# XPDR_Board_1.net
KiCad netlist of a schematic drawn in EAGLE
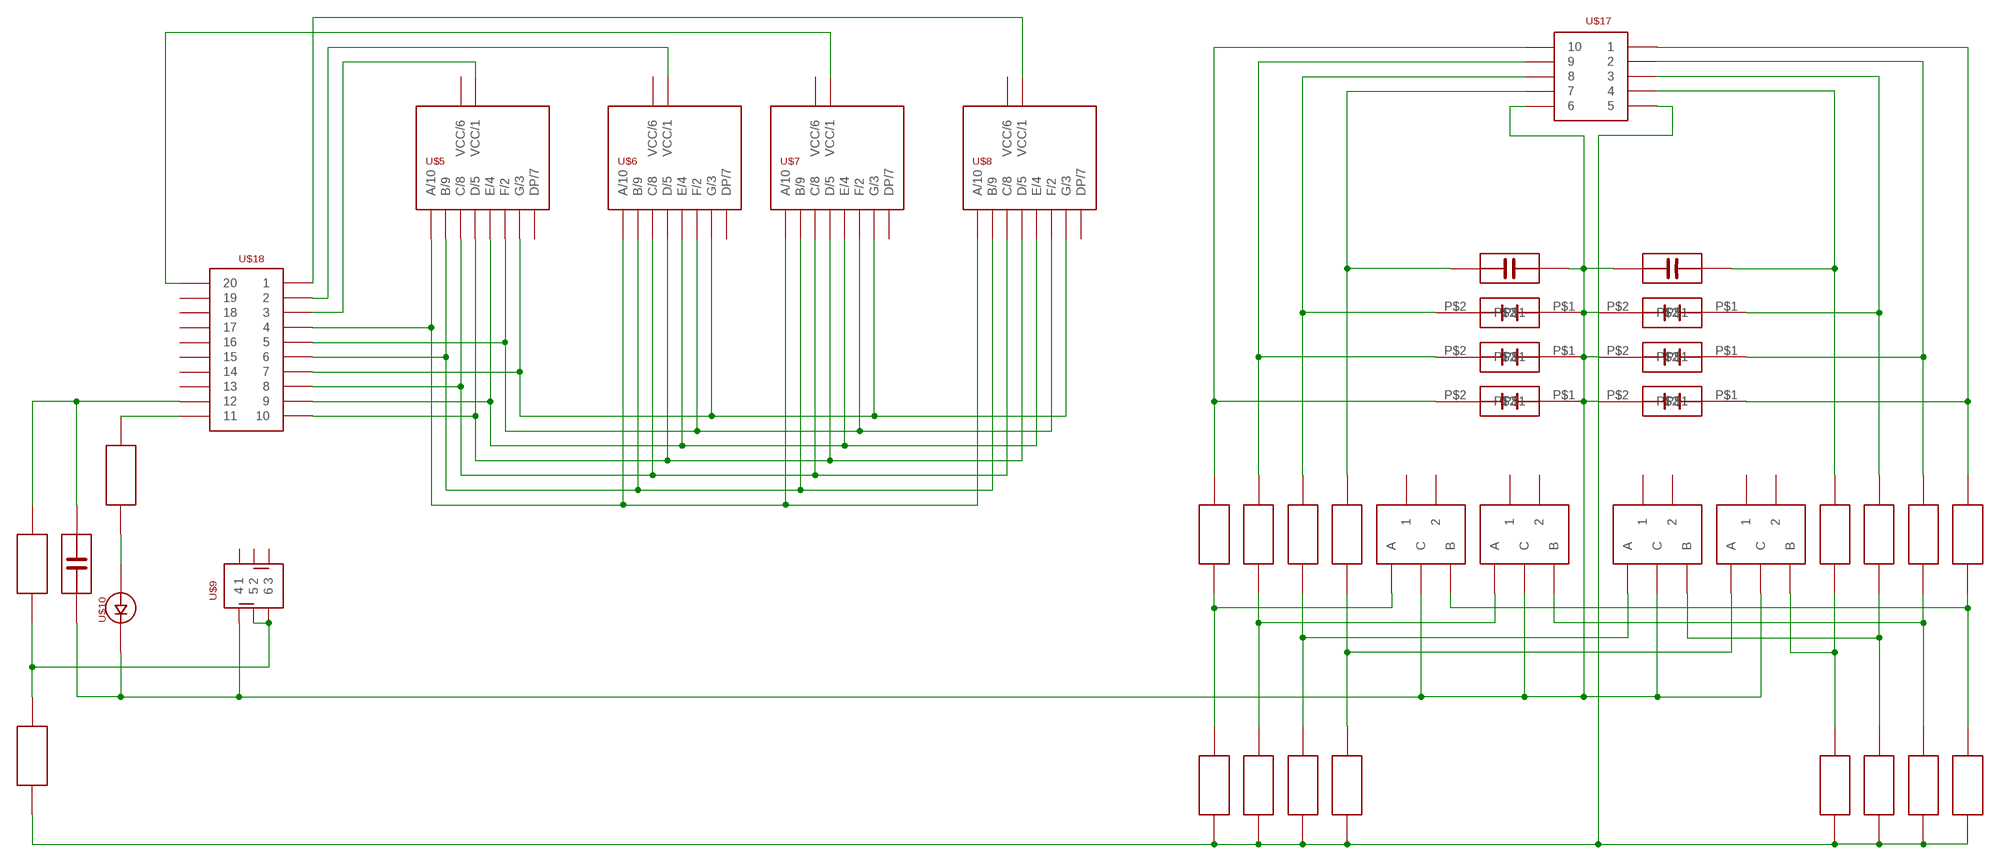
[diagram p0: schematic, sheet 1]

(export (version "E")
  (design (tool "Eeschema 10.0.6"))
  (components
    (comp (ref "U$1")
      (value "PEC11R")
      (footprint "eagle-import:PEC11R")
      (libsource (lib "eagle-import") (part "PEC11R"))
    )
    (comp (ref "U$2")
      (value "PEC11R")
      (footprint "eagle-import:PEC11R")
      (libsource (lib "eagle-import") (part "PEC11R"))
    )
    (comp (ref "U$3")
      (value "PEC11R")
      (footprint "eagle-import:PEC11R")
      (libsource (lib "eagle-import") (part "PEC11R"))
    )
    (comp (ref "U$4")
      (value "PEC11R")
      (footprint "eagle-import:PEC11R")
      (libsource (lib "eagle-import") (part "PEC11R"))
    )
    (comp (ref "U$5")
      (value "SA3611EWA")
      (footprint "eagle-import:SA3611EWA")
      (libsource (lib "eagle-import") (part "SA3611EWA"))
    )
    (comp (ref "U$6")
      (value "SA3611EWA")
      (footprint "eagle-import:SA3611EWA")
      (libsource (lib "eagle-import") (part "SA3611EWA"))
    )
    (comp (ref "U$7")
      (value "SA3611EWA")
      (footprint "eagle-import:SA3611EWA")
      (libsource (lib "eagle-import") (part "SA3611EWA"))
    )
    (comp (ref "U$8")
      (value "SA3611EWA")
      (footprint "eagle-import:SA3611EWA")
      (libsource (lib "eagle-import") (part "SA3611EWA"))
    )
    (comp (ref "U$9")
      (value "P1-0S")
      (footprint "eagle-import:P1-0S")
      (libsource (lib "eagle-import") (part "P1-0S"))
    )
    (comp (ref "U$10")
      (value "LED_5MM")
      (footprint "eagle-import:LED_5MM")
      (libsource (lib "eagle-import") (part "LED_5MM"))
    )
    (comp (ref "U$11")
      (value "REZISTOR")
      (footprint "eagle-import:REZISTOR")
      (libsource (lib "eagle-import") (part "REZISTOR"))
    )
    (comp (ref "U$12")
      (value "REZISTOR")
      (footprint "eagle-import:REZISTOR")
      (libsource (lib "eagle-import") (part "REZISTOR"))
    )
    (comp (ref "U$13")
      (value "REZISTOR")
      (footprint "eagle-import:REZISTOR")
      (libsource (lib "eagle-import") (part "REZISTOR"))
    )
    (comp (ref "U$14")
      (value "REZISTOR")
      (footprint "eagle-import:REZISTOR")
      (libsource (lib "eagle-import") (part "REZISTOR"))
    )
    (comp (ref "U$15")
      (value "REZISTOR")
      (footprint "eagle-import:REZISTOR")
      (libsource (lib "eagle-import") (part "REZISTOR"))
    )
    (comp (ref "U$16")
      (value "REZISTOR")
      (footprint "eagle-import:REZISTOR")
      (libsource (lib "eagle-import") (part "REZISTOR"))
    )
    (comp (ref "U$17")
      (value "LISTA_2X5")
      (footprint "eagle-import:LISTA_2X5")
      (libsource (lib "eagle-import") (part "LISTA_2X5"))
    )
    (comp (ref "U$18")
      (value "LISTA_2X10")
      (footprint "eagle-import:LISTA_2X10")
      (libsource (lib "eagle-import") (part "LISTA_2X10"))
    )
    (comp (ref "U$19")
      (value "REZISTOR")
      (footprint "eagle-import:REZISTOR")
      (libsource (lib "eagle-import") (part "REZISTOR"))
    )
    (comp (ref "U$20")
      (value "REZISTOR")
      (footprint "eagle-import:REZISTOR")
      (libsource (lib "eagle-import") (part "REZISTOR"))
    )
    (comp (ref "U$21")
      (value "REZISTOR")
      (footprint "eagle-import:REZISTOR")
      (libsource (lib "eagle-import") (part "REZISTOR"))
    )
    (comp (ref "U$22")
      (value "REZISTOR")
      (footprint "eagle-import:REZISTOR")
      (libsource (lib "eagle-import") (part "REZISTOR"))
    )
    (comp (ref "U$23")
      (value "REZISTOR")
      (footprint "eagle-import:REZISTOR")
      (libsource (lib "eagle-import") (part "REZISTOR"))
    )
    (comp (ref "U$24")
      (value "REZISTOR")
      (footprint "eagle-import:REZISTOR")
      (libsource (lib "eagle-import") (part "REZISTOR"))
    )
    (comp (ref "U$25")
      (value "REZISTOR")
      (footprint "eagle-import:REZISTOR")
      (libsource (lib "eagle-import") (part "REZISTOR"))
    )
    (comp (ref "U$26")
      (value "REZISTOR")
      (footprint "eagle-import:REZISTOR")
      (libsource (lib "eagle-import") (part "REZISTOR"))
    )
    (comp (ref "U$27")
      (value "REZISTOR")
      (footprint "eagle-import:REZISTOR")
      (libsource (lib "eagle-import") (part "REZISTOR"))
    )
    (comp (ref "U$28")
      (value "REZISTOR")
      (footprint "eagle-import:REZISTOR")
      (libsource (lib "eagle-import") (part "REZISTOR"))
    )
    (comp (ref "U$29")
      (value "KONDENZATOR_SIROKY")
      (footprint "eagle-import:KONDENZATOR_SIROKY")
      (libsource (lib "eagle-import") (part "KONDENZATOR_SIROKY"))
    )
    (comp (ref "U$30")
      (value "REZISTOR")
      (footprint "eagle-import:REZISTOR")
      (libsource (lib "eagle-import") (part "REZISTOR"))
    )
    (comp (ref "U$31")
      (value "REZISTOR")
      (footprint "eagle-import:REZISTOR")
      (libsource (lib "eagle-import") (part "REZISTOR"))
    )
    (comp (ref "U$32")
      (value "KONDENZATOR_SIROKY")
      (footprint "eagle-import:KONDENZATOR_SIROKY")
      (libsource (lib "eagle-import") (part "KONDENZATOR_SIROKY"))
    )
    (comp (ref "U$33")
      (value "KONDENZATOR_SIROKY")
      (footprint "eagle-import:KONDENZATOR_SIROKY")
      (libsource (lib "eagle-import") (part "KONDENZATOR_SIROKY"))
    )
    (comp (ref "U$34")
      (value "KONDENZATOR")
      (footprint "eagle-import:KONDENZATOR")
      (libsource (lib "eagle-import") (part "KONDENZATOR"))
    )
    (comp (ref "U$35")
      (value "KONDENZATOR_SIROKY")
      (footprint "eagle-import:KONDENZATOR_SIROKY")
      (libsource (lib "eagle-import") (part "KONDENZATOR_SIROKY"))
    )
    (comp (ref "U$36")
      (value "KONDENZATOR_SIROKY")
      (footprint "eagle-import:KONDENZATOR_SIROKY")
      (libsource (lib "eagle-import") (part "KONDENZATOR_SIROKY"))
    )
    (comp (ref "U$37")
      (value "KONDENZATOR_SIROKY")
      (footprint "eagle-import:KONDENZATOR_SIROKY")
      (libsource (lib "eagle-import") (part "KONDENZATOR_SIROKY"))
    )
    (comp (ref "U$38")
      (value "KONDENZATOR")
      (footprint "eagle-import:KONDENZATOR")
      (libsource (lib "eagle-import") (part "KONDENZATOR"))
    )
    (comp (ref "U$39")
      (value "KONDENZATOR")
      (footprint "eagle-import:KONDENZATOR")
      (libsource (lib "eagle-import") (part "KONDENZATOR"))
    )
    (comp (ref "U$40")
      (value "REZISTOR")
      (footprint "eagle-import:REZISTOR")
      (libsource (lib "eagle-import") (part "REZISTOR"))
    )
  )
  (nets
    (net (code "1") (name "Net-(U$1-PadA)") (class "Default")
      (node (ref "U$1") (pin "A") (pinfunction "A_A") (pintype "bidirectional"))
      (node (ref "U$11") (pin "P$1") (pinfunction "P$1_P$1") (pintype "bidirectional"))
      (node (ref "U$28") (pin "P$1") (pinfunction "P$1_P$1") (pintype "bidirectional"))
    )
    (net (code "2") (name "Net-(U$1-PadB)") (class "Default")
      (node (ref "U$1") (pin "B") (pinfunction "B_B") (pintype "bidirectional"))
      (node (ref "U$12") (pin "P$1") (pinfunction "P$1_P$1") (pintype "bidirectional"))
      (node (ref "U$27") (pin "P$1") (pinfunction "P$1_P$1") (pintype "bidirectional"))
    )
    (net (code "3") (name "Net-(U$1-PadC)") (class "Default")
      (node (ref "U$1") (pin "C") (pinfunction "C_C") (pintype "bidirectional"))
      (node (ref "U$10") (pin "P$2") (pinfunction "P$2_P$2") (pintype "bidirectional"))
      (node (ref "U$17") (pin "6") (pinfunction "6_6") (pintype "bidirectional"))
      (node (ref "U$2") (pin "C") (pinfunction "C_C") (pintype "bidirectional"))
      (node (ref "U$29") (pin "P$1") (pinfunction "P$1_P$1") (pintype "bidirectional"))
      (node (ref "U$3") (pin "C") (pinfunction "C_C") (pintype "bidirectional"))
      (node (ref "U$32") (pin "P$1") (pinfunction "P$1_P$1") (pintype "bidirectional"))
      (node (ref "U$33") (pin "P$1") (pinfunction "P$1_P$1") (pintype "bidirectional"))
      (node (ref "U$34") (pin "P$1") (pinfunction "P$1_P$1") (pintype "bidirectional"))
      (node (ref "U$35") (pin "P$2") (pinfunction "P$2_P$2") (pintype "bidirectional"))
      (node (ref "U$36") (pin "P$2") (pinfunction "P$2_P$2") (pintype "bidirectional"))
      (node (ref "U$37") (pin "P$2") (pinfunction "P$2_P$2") (pintype "bidirectional"))
      (node (ref "U$38") (pin "P$2") (pinfunction "P$2_P$2") (pintype "bidirectional"))
      (node (ref "U$39") (pin "P$2") (pinfunction "P$2_P$2") (pintype "bidirectional"))
      (node (ref "U$4") (pin "C") (pinfunction "C_C") (pintype "bidirectional"))
      (node (ref "U$9") (pin "4") (pinfunction "4_4") (pintype "bidirectional"))
    )
    (net (code "4") (name "Net-(U$5-A{slash}10)") (class "Default")
      (node (ref "U$18") (pin "4") (pinfunction "4_4") (pintype "bidirectional"))
      (node (ref "U$5") (pin "10") (pinfunction "A/10_10") (pintype "bidirectional"))
      (node (ref "U$6") (pin "10") (pinfunction "A/10_10") (pintype "bidirectional"))
      (node (ref "U$7") (pin "10") (pinfunction "A/10_10") (pintype "bidirectional"))
      (node (ref "U$8") (pin "10") (pinfunction "A/10_10") (pintype "bidirectional"))
    )
    (net (code "5") (name "Net-(U$5-B{slash}9)") (class "Default")
      (node (ref "U$18") (pin "6") (pinfunction "6_6") (pintype "bidirectional"))
      (node (ref "U$5") (pin "9") (pinfunction "B/9_9") (pintype "bidirectional"))
      (node (ref "U$6") (pin "9") (pinfunction "B/9_9") (pintype "bidirectional"))
      (node (ref "U$7") (pin "9") (pinfunction "B/9_9") (pintype "bidirectional"))
      (node (ref "U$8") (pin "9") (pinfunction "B/9_9") (pintype "bidirectional"))
    )
    (net (code "6") (name "Net-(U$5-C{slash}8)") (class "Default")
      (node (ref "U$18") (pin "8") (pinfunction "8_8") (pintype "bidirectional"))
      (node (ref "U$5") (pin "8") (pinfunction "C/8_8") (pintype "bidirectional"))
      (node (ref "U$6") (pin "8") (pinfunction "C/8_8") (pintype "bidirectional"))
      (node (ref "U$7") (pin "8") (pinfunction "C/8_8") (pintype "bidirectional"))
      (node (ref "U$8") (pin "8") (pinfunction "C/8_8") (pintype "bidirectional"))
    )
    (net (code "7") (name "Net-(U$5-D{slash}5)") (class "Default")
      (node (ref "U$18") (pin "10") (pinfunction "10_10") (pintype "bidirectional"))
      (node (ref "U$5") (pin "5") (pinfunction "D/5_5") (pintype "bidirectional"))
      (node (ref "U$6") (pin "5") (pinfunction "D/5_5") (pintype "bidirectional"))
      (node (ref "U$7") (pin "5") (pinfunction "D/5_5") (pintype "bidirectional"))
      (node (ref "U$8") (pin "5") (pinfunction "D/5_5") (pintype "bidirectional"))
    )
    (net (code "8") (name "Net-(U$5-E{slash}4)") (class "Default")
      (node (ref "U$18") (pin "9") (pinfunction "9_9") (pintype "bidirectional"))
      (node (ref "U$5") (pin "4") (pinfunction "E/4_4") (pintype "bidirectional"))
      (node (ref "U$6") (pin "4") (pinfunction "E/4_4") (pintype "bidirectional"))
      (node (ref "U$7") (pin "4") (pinfunction "E/4_4") (pintype "bidirectional"))
      (node (ref "U$8") (pin "4") (pinfunction "E/4_4") (pintype "bidirectional"))
    )
    (net (code "9") (name "Net-(U$5-F{slash}2)") (class "Default")
      (node (ref "U$18") (pin "5") (pinfunction "5_5") (pintype "bidirectional"))
      (node (ref "U$5") (pin "2") (pinfunction "F/2_2") (pintype "bidirectional"))
      (node (ref "U$6") (pin "2") (pinfunction "F/2_2") (pintype "bidirectional"))
      (node (ref "U$7") (pin "2") (pinfunction "F/2_2") (pintype "bidirectional"))
      (node (ref "U$8") (pin "2") (pinfunction "F/2_2") (pintype "bidirectional"))
    )
    (net (code "10") (name "Net-(U$5-G{slash}3)") (class "Default")
      (node (ref "U$18") (pin "7") (pinfunction "7_7") (pintype "bidirectional"))
      (node (ref "U$5") (pin "3") (pinfunction "G/3_3") (pintype "bidirectional"))
      (node (ref "U$6") (pin "3") (pinfunction "G/3_3") (pintype "bidirectional"))
      (node (ref "U$7") (pin "3") (pinfunction "G/3_3") (pintype "bidirectional"))
      (node (ref "U$8") (pin "3") (pinfunction "G/3_3") (pintype "bidirectional"))
    )
    (net (code "11") (name "Net-(U$5-VCC{slash}1)") (class "Default")
      (node (ref "U$18") (pin "3") (pinfunction "3_3") (pintype "bidirectional"))
      (node (ref "U$5") (pin "1") (pinfunction "VCC/1_1") (pintype "bidirectional"))
    )
    (net (code "12") (name "Net-(U$6-VCC{slash}1)") (class "Default")
      (node (ref "U$18") (pin "2") (pinfunction "2_2") (pintype "bidirectional"))
      (node (ref "U$6") (pin "1") (pinfunction "VCC/1_1") (pintype "bidirectional"))
    )
    (net (code "13") (name "Net-(U$7-VCC{slash}1)") (class "Default")
      (node (ref "U$18") (pin "20") (pinfunction "20_20") (pintype "bidirectional"))
      (node (ref "U$7") (pin "1") (pinfunction "VCC/1_1") (pintype "bidirectional"))
    )
    (net (code "14") (name "Net-(U$8-VCC{slash}1)") (class "Default")
      (node (ref "U$18") (pin "1") (pinfunction "1_1") (pintype "bidirectional"))
      (node (ref "U$8") (pin "1") (pinfunction "VCC/1_1") (pintype "bidirectional"))
    )
    (net (code "15") (name "Net-(U$10-PadP$1)") (class "Default")
      (node (ref "U$10") (pin "P$1") (pinfunction "P$1_P$1") (pintype "bidirectional"))
      (node (ref "U$40") (pin "P$2") (pinfunction "P$2_P$2") (pintype "bidirectional"))
    )
    (net (code "16") (name "Net-(U$11-PadP$2)") (class "Default")
      (node (ref "U$11") (pin "P$2") (pinfunction "P$2_P$2") (pintype "bidirectional"))
      (node (ref "U$17") (pin "10") (pinfunction "10_10") (pintype "bidirectional"))
      (node (ref "U$29") (pin "P$2") (pinfunction "P$2_P$2") (pintype "bidirectional"))
    )
    (net (code "17") (name "Net-(U$12-PadP$2)") (class "Default")
      (node (ref "U$12") (pin "P$2") (pinfunction "P$2_P$2") (pintype "bidirectional"))
      (node (ref "U$17") (pin "1") (pinfunction "1_1") (pintype "bidirectional"))
      (node (ref "U$35") (pin "P$1") (pinfunction "P$1_P$1") (pintype "bidirectional"))
    )
    (net (code "18") (name "Net-(U$13-PadP$1)") (class "Default")
      (node (ref "U$13") (pin "P$1") (pinfunction "P$1_P$1") (pintype "bidirectional"))
      (node (ref "U$2") (pin "A") (pinfunction "A_A") (pintype "bidirectional"))
      (node (ref "U$26") (pin "P$1") (pinfunction "P$1_P$1") (pintype "bidirectional"))
    )
    (net (code "19") (name "Net-(U$13-PadP$2)") (class "Default")
      (node (ref "U$13") (pin "P$2") (pinfunction "P$2_P$2") (pintype "bidirectional"))
      (node (ref "U$17") (pin "9") (pinfunction "9_9") (pintype "bidirectional"))
      (node (ref "U$32") (pin "P$2") (pinfunction "P$2_P$2") (pintype "bidirectional"))
    )
    (net (code "20") (name "Net-(U$14-PadP$1)") (class "Default")
      (node (ref "U$14") (pin "P$1") (pinfunction "P$1_P$1") (pintype "bidirectional"))
      (node (ref "U$2") (pin "B") (pinfunction "B_B") (pintype "bidirectional"))
      (node (ref "U$25") (pin "P$1") (pinfunction "P$1_P$1") (pintype "bidirectional"))
    )
    (net (code "21") (name "Net-(U$14-PadP$2)") (class "Default")
      (node (ref "U$14") (pin "P$2") (pinfunction "P$2_P$2") (pintype "bidirectional"))
      (node (ref "U$17") (pin "2") (pinfunction "2_2") (pintype "bidirectional"))
      (node (ref "U$36") (pin "P$1") (pinfunction "P$1_P$1") (pintype "bidirectional"))
    )
    (net (code "22") (name "Net-(U$15-PadP$1)") (class "Default")
      (node (ref "U$15") (pin "P$1") (pinfunction "P$1_P$1") (pintype "bidirectional"))
      (node (ref "U$24") (pin "P$1") (pinfunction "P$1_P$1") (pintype "bidirectional"))
      (node (ref "U$3") (pin "A") (pinfunction "A_A") (pintype "bidirectional"))
    )
    (net (code "23") (name "Net-(U$15-PadP$2)") (class "Default")
      (node (ref "U$15") (pin "P$2") (pinfunction "P$2_P$2") (pintype "bidirectional"))
      (node (ref "U$17") (pin "8") (pinfunction "8_8") (pintype "bidirectional"))
      (node (ref "U$33") (pin "P$2") (pinfunction "P$2_P$2") (pintype "bidirectional"))
    )
    (net (code "24") (name "Net-(U$16-PadP$1)") (class "Default")
      (node (ref "U$16") (pin "P$1") (pinfunction "P$1_P$1") (pintype "bidirectional"))
      (node (ref "U$23") (pin "P$1") (pinfunction "P$1_P$1") (pintype "bidirectional"))
      (node (ref "U$3") (pin "B") (pinfunction "B_B") (pintype "bidirectional"))
    )
    (net (code "25") (name "Net-(U$16-PadP$2)") (class "Default")
      (node (ref "U$16") (pin "P$2") (pinfunction "P$2_P$2") (pintype "bidirectional"))
      (node (ref "U$17") (pin "3") (pinfunction "3_3") (pintype "bidirectional"))
      (node (ref "U$37") (pin "P$1") (pinfunction "P$1_P$1") (pintype "bidirectional"))
    )
    (net (code "26") (name "Net-(U$17-Pad4)") (class "Default")
      (node (ref "U$17") (pin "4") (pinfunction "4_4") (pintype "bidirectional"))
      (node (ref "U$20") (pin "P$2") (pinfunction "P$2_P$2") (pintype "bidirectional"))
      (node (ref "U$38") (pin "P$1") (pinfunction "P$1_P$1") (pintype "bidirectional"))
    )
    (net (code "27") (name "Net-(U$17-Pad5)") (class "Default")
      (node (ref "U$17") (pin "5") (pinfunction "5_5") (pintype "bidirectional"))
      (node (ref "U$21") (pin "P$2") (pinfunction "P$2_P$2") (pintype "bidirectional"))
      (node (ref "U$22") (pin "P$2") (pinfunction "P$2_P$2") (pintype "bidirectional"))
      (node (ref "U$23") (pin "P$2") (pinfunction "P$2_P$2") (pintype "bidirectional"))
      (node (ref "U$24") (pin "P$2") (pinfunction "P$2_P$2") (pintype "bidirectional"))
      (node (ref "U$25") (pin "P$2") (pinfunction "P$2_P$2") (pintype "bidirectional"))
      (node (ref "U$26") (pin "P$2") (pinfunction "P$2_P$2") (pintype "bidirectional"))
      (node (ref "U$27") (pin "P$2") (pinfunction "P$2_P$2") (pintype "bidirectional"))
      (node (ref "U$28") (pin "P$2") (pinfunction "P$2_P$2") (pintype "bidirectional"))
      (node (ref "U$31") (pin "P$2") (pinfunction "P$2_P$2") (pintype "bidirectional"))
    )
    (net (code "28") (name "Net-(U$17-Pad7)") (class "Default")
      (node (ref "U$17") (pin "7") (pinfunction "7_7") (pintype "bidirectional"))
      (node (ref "U$19") (pin "P$2") (pinfunction "P$2_P$2") (pintype "bidirectional"))
      (node (ref "U$34") (pin "P$2") (pinfunction "P$2_P$2") (pintype "bidirectional"))
    )
    (net (code "29") (name "Net-(U$18-Pad11)") (class "Default")
      (node (ref "U$18") (pin "11") (pinfunction "11_11") (pintype "bidirectional"))
      (node (ref "U$40") (pin "P$1") (pinfunction "P$1_P$1") (pintype "bidirectional"))
    )
    (net (code "30") (name "Net-(U$18-Pad12)") (class "Default")
      (node (ref "U$18") (pin "12") (pinfunction "12_12") (pintype "bidirectional"))
      (node (ref "U$30") (pin "P$1") (pinfunction "P$1_P$1") (pintype "bidirectional"))
      (node (ref "U$39") (pin "P$1") (pinfunction "P$1_P$1") (pintype "bidirectional"))
    )
    (net (code "31") (name "Net-(U$19-PadP$1)") (class "Default")
      (node (ref "U$19") (pin "P$1") (pinfunction "P$1_P$1") (pintype "bidirectional"))
      (node (ref "U$22") (pin "P$1") (pinfunction "P$1_P$1") (pintype "bidirectional"))
      (node (ref "U$4") (pin "A") (pinfunction "A_A") (pintype "bidirectional"))
    )
    (net (code "32") (name "Net-(U$20-PadP$1)") (class "Default")
      (node (ref "U$20") (pin "P$1") (pinfunction "P$1_P$1") (pintype "bidirectional"))
      (node (ref "U$21") (pin "P$1") (pinfunction "P$1_P$1") (pintype "bidirectional"))
      (node (ref "U$4") (pin "B") (pinfunction "B_B") (pintype "bidirectional"))
    )
    (net (code "33") (name "Net-(U$30-PadP$2)") (class "Default")
      (node (ref "U$30") (pin "P$2") (pinfunction "P$2_P$2") (pintype "bidirectional"))
      (node (ref "U$31") (pin "P$1") (pinfunction "P$1_P$1") (pintype "bidirectional"))
      (node (ref "U$9") (pin "5") (pinfunction "5_5") (pintype "bidirectional"))
      (node (ref "U$9") (pin "6") (pinfunction "6_6") (pintype "bidirectional"))
    )
    (net (code "34") (name "unconnected-(U$1-Pad1)") (class "Default")
      (node (ref "U$1") (pin "1") (pinfunction "1_1") (pintype "bidirectional"))
    )
    (net (code "35") (name "unconnected-(U$1-Pad2)") (class "Default")
      (node (ref "U$1") (pin "2") (pinfunction "2_2") (pintype "bidirectional"))
    )
    (net (code "36") (name "unconnected-(U$2-Pad1)") (class "Default")
      (node (ref "U$2") (pin "1") (pinfunction "1_1") (pintype "bidirectional"))
    )
    (net (code "37") (name "unconnected-(U$2-Pad2)") (class "Default")
      (node (ref "U$2") (pin "2") (pinfunction "2_2") (pintype "bidirectional"))
    )
    (net (code "38") (name "unconnected-(U$3-Pad1)") (class "Default")
      (node (ref "U$3") (pin "1") (pinfunction "1_1") (pintype "bidirectional"))
    )
    (net (code "39") (name "unconnected-(U$3-Pad2)") (class "Default")
      (node (ref "U$3") (pin "2") (pinfunction "2_2") (pintype "bidirectional"))
    )
    (net (code "40") (name "unconnected-(U$4-Pad1)") (class "Default")
      (node (ref "U$4") (pin "1") (pinfunction "1_1") (pintype "bidirectional"))
    )
    (net (code "41") (name "unconnected-(U$4-Pad2)") (class "Default")
      (node (ref "U$4") (pin "2") (pinfunction "2_2") (pintype "bidirectional"))
    )
    (net (code "42") (name "unconnected-(U$5-DP{slash}7-Pad7)") (class "Default")
      (node (ref "U$5") (pin "7") (pinfunction "DP/7_7") (pintype "bidirectional"))
    )
    (net (code "43") (name "unconnected-(U$5-VCC{slash}6-Pad6)") (class "Default")
      (node (ref "U$5") (pin "6") (pinfunction "VCC/6_6") (pintype "bidirectional"))
    )
    (net (code "44") (name "unconnected-(U$6-DP{slash}7-Pad7)") (class "Default")
      (node (ref "U$6") (pin "7") (pinfunction "DP/7_7") (pintype "bidirectional"))
    )
    (net (code "45") (name "unconnected-(U$6-VCC{slash}6-Pad6)") (class "Default")
      (node (ref "U$6") (pin "6") (pinfunction "VCC/6_6") (pintype "bidirectional"))
    )
    (net (code "46") (name "unconnected-(U$7-DP{slash}7-Pad7)") (class "Default")
      (node (ref "U$7") (pin "7") (pinfunction "DP/7_7") (pintype "bidirectional"))
    )
    (net (code "47") (name "unconnected-(U$7-VCC{slash}6-Pad6)") (class "Default")
      (node (ref "U$7") (pin "6") (pinfunction "VCC/6_6") (pintype "bidirectional"))
    )
    (net (code "48") (name "unconnected-(U$8-DP{slash}7-Pad7)") (class "Default")
      (node (ref "U$8") (pin "7") (pinfunction "DP/7_7") (pintype "bidirectional"))
    )
    (net (code "49") (name "unconnected-(U$8-VCC{slash}6-Pad6)") (class "Default")
      (node (ref "U$8") (pin "6") (pinfunction "VCC/6_6") (pintype "bidirectional"))
    )
    (net (code "50") (name "unconnected-(U$9-Pad1)") (class "Default")
      (node (ref "U$9") (pin "1") (pinfunction "1_1") (pintype "bidirectional"))
    )
    (net (code "51") (name "unconnected-(U$9-Pad2)") (class "Default")
      (node (ref "U$9") (pin "2") (pinfunction "2_2") (pintype "bidirectional"))
    )
    (net (code "52") (name "unconnected-(U$9-Pad3)") (class "Default")
      (node (ref "U$9") (pin "3") (pinfunction "3_3") (pintype "bidirectional"))
    )
    (net (code "53") (name "unconnected-(U$18-Pad13)") (class "Default")
      (node (ref "U$18") (pin "13") (pinfunction "13_13") (pintype "bidirectional"))
    )
    (net (code "54") (name "unconnected-(U$18-Pad14)") (class "Default")
      (node (ref "U$18") (pin "14") (pinfunction "14_14") (pintype "bidirectional"))
    )
    (net (code "55") (name "unconnected-(U$18-Pad15)") (class "Default")
      (node (ref "U$18") (pin "15") (pinfunction "15_15") (pintype "bidirectional"))
    )
    (net (code "56") (name "unconnected-(U$18-Pad16)") (class "Default")
      (node (ref "U$18") (pin "16") (pinfunction "16_16") (pintype "bidirectional"))
    )
    (net (code "57") (name "unconnected-(U$18-Pad17)") (class "Default")
      (node (ref "U$18") (pin "17") (pinfunction "17_17") (pintype "bidirectional"))
    )
    (net (code "58") (name "unconnected-(U$18-Pad18)") (class "Default")
      (node (ref "U$18") (pin "18") (pinfunction "18_18") (pintype "bidirectional"))
    )
    (net (code "59") (name "unconnected-(U$18-Pad19)") (class "Default")
      (node (ref "U$18") (pin "19") (pinfunction "19_19") (pintype "bidirectional"))
    )
  )
)
